# 23XXAdapter.net
KiCad netlist of a schematic drawn in EAGLE
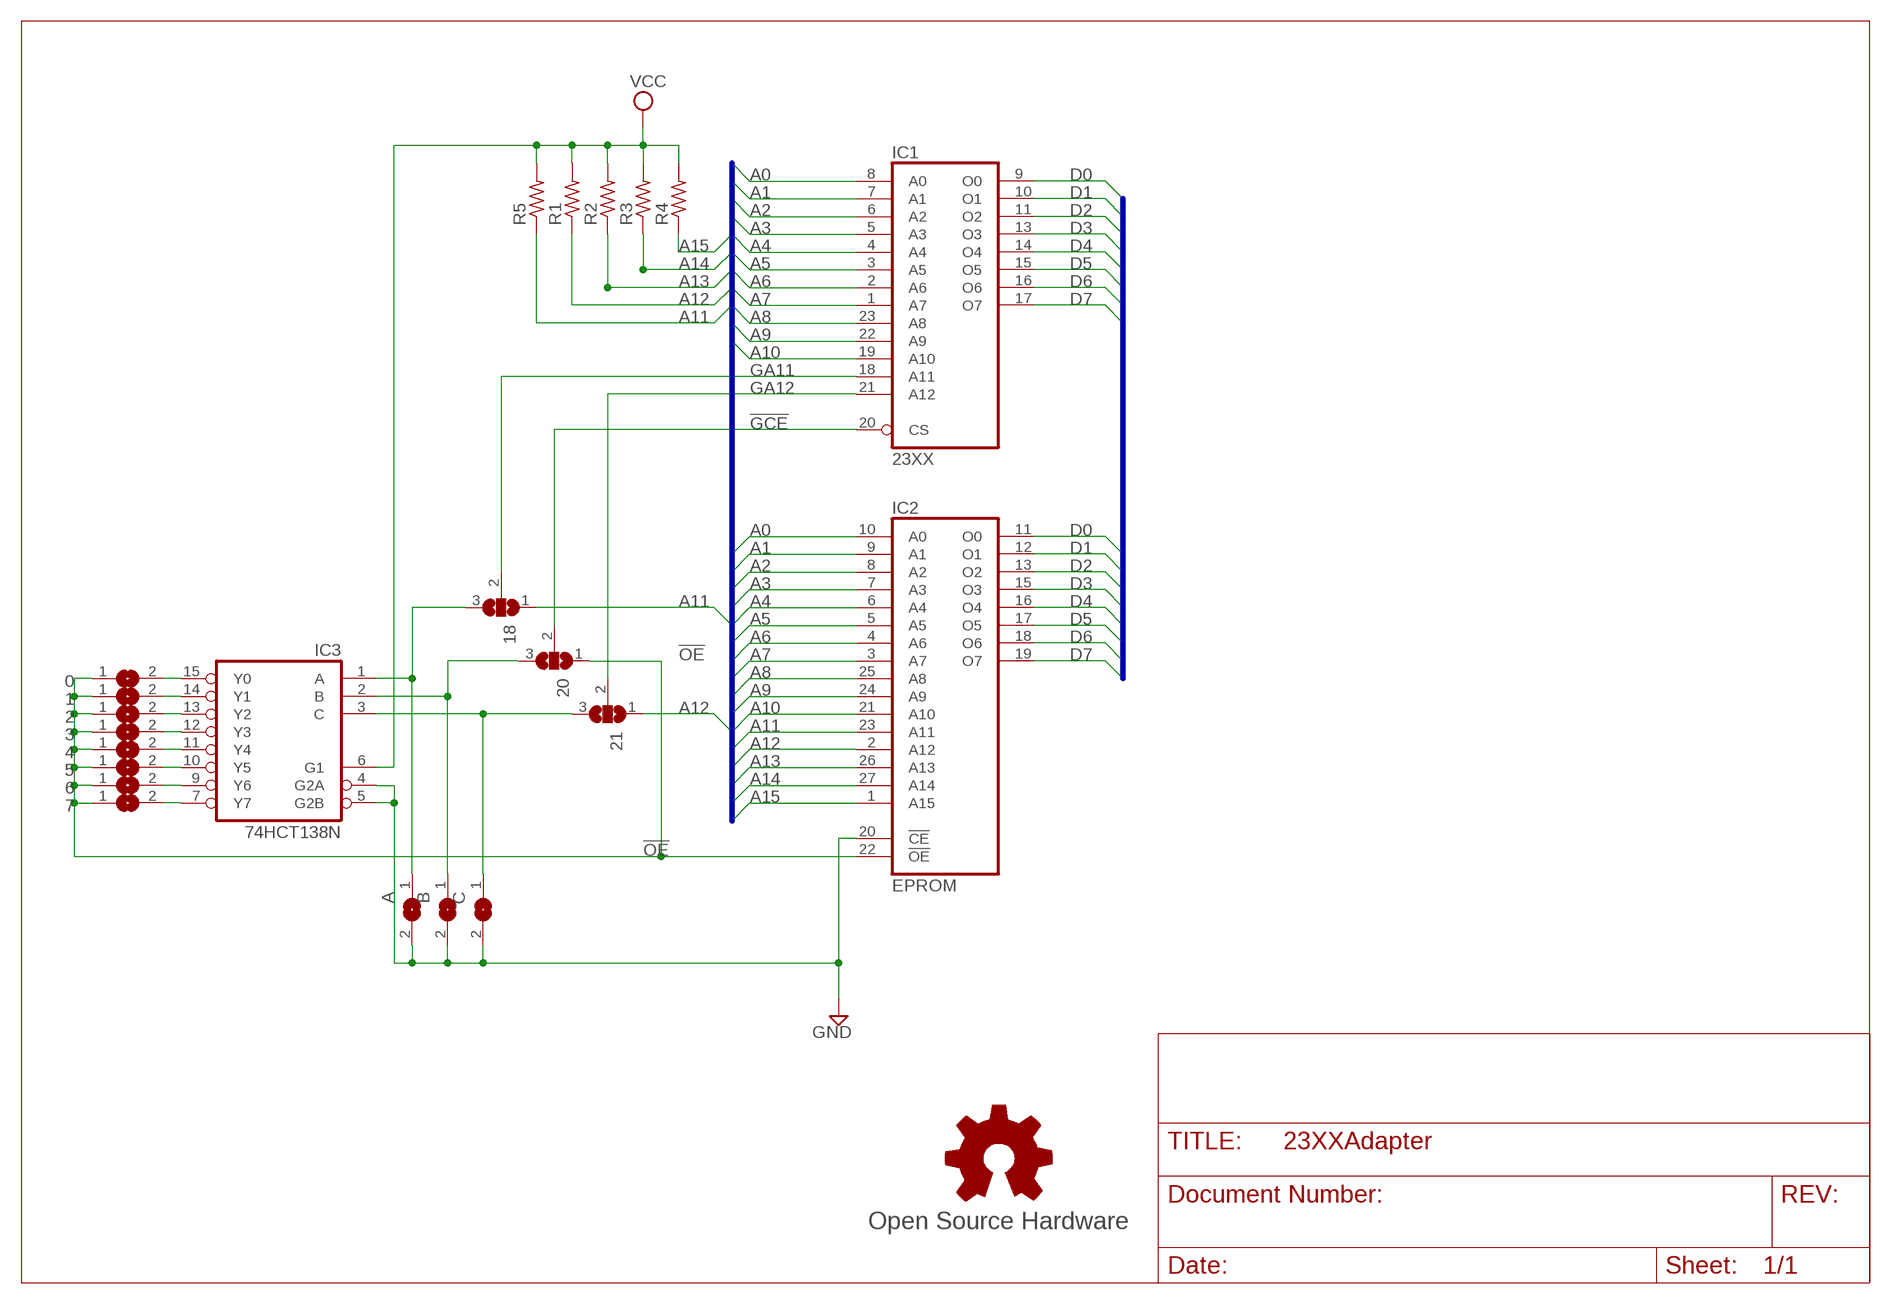
[diagram p0: schematic, sheet 1]

(export (version "E")
  (design (tool "Eeschema 10.0.6"))
  (components
    (comp (ref "0") (value "SJ") (footprint "eagle-import:SJ") (libsource (lib "eagle-import") (part "SJ")))
    (comp (ref "1") (value "SJ") (footprint "eagle-import:SJ") (libsource (lib "eagle-import") (part "SJ")))
    (comp (ref "2") (value "SJ") (footprint "eagle-import:SJ") (libsource (lib "eagle-import") (part "SJ")))
    (comp (ref "3") (value "SJ") (footprint "eagle-import:SJ") (libsource (lib "eagle-import") (part "SJ")))
    (comp (ref "4") (value "SJ") (footprint "eagle-import:SJ") (libsource (lib "eagle-import") (part "SJ")))
    (comp (ref "5") (value "SJ") (footprint "eagle-import:SJ") (libsource (lib "eagle-import") (part "SJ")))
    (comp (ref "6") (value "SJ") (footprint "eagle-import:SJ") (libsource (lib "eagle-import") (part "SJ")))
    (comp (ref "7") (value "SJ") (footprint "eagle-import:SJ") (libsource (lib "eagle-import") (part "SJ")))
    (comp (ref "18")
      (value "SJ2W")
      (footprint "eagle-import:SJ_2")
      (libsource (lib "eagle-import") (part "SJ2W"))
    )
    (comp (ref "20")
      (value "SJ2W")
      (footprint "eagle-import:SJ_2")
      (libsource (lib "eagle-import") (part "SJ2W"))
    )
    (comp (ref "21")
      (value "SJ2W")
      (footprint "eagle-import:SJ_2")
      (libsource (lib "eagle-import") (part "SJ2W"))
    )
    (comp (ref "A") (value "SJ") (footprint "eagle-import:SJ") (libsource (lib "eagle-import") (part "SJ")))
    (comp (ref "B") (value "SJ") (footprint "eagle-import:SJ") (libsource (lib "eagle-import") (part "SJ")))
    (comp (ref "C") (value "SJ") (footprint "eagle-import:SJ") (libsource (lib "eagle-import") (part "SJ")))
    (comp (ref "GOLD_ORB_SM1")
      (value "Open Source Hardware")
      (footprint "eagle-import:OSHW_5MM")
      (libsource (lib "eagle-import") (part "OSHWLOGOLOGO5MM"))
    )
    (comp (ref "IC1")
      (value "23XX")
      (footprint "eagle-import:DIL24-ROUNDPAD")
      (libsource (lib "eagle-import") (part "2364'RD'"))
    )
    (comp (ref "IC2")
      (value "EPROM")
      (footprint "eagle-import:DIL28-ROUNDPAD")
      (libsource (lib "eagle-import") (part "27512'RD'"))
    )
    (comp (ref "IC3")
      (value "74HCT138N")
      (footprint "eagle-import:DIL16")
      (libsource (lib "eagle-import") (part "74138NLS"))
    )
    (comp (ref "R1")
      (value "R-US_0204/5")
      (footprint "eagle-import:0204_5")
      (libsource (lib "eagle-import") (part "R-US_0204/5"))
    )
    (comp (ref "R2")
      (value "R-US_0204/5")
      (footprint "eagle-import:0204_5")
      (libsource (lib "eagle-import") (part "R-US_0204/5"))
    )
    (comp (ref "R3")
      (value "R-US_0204/5")
      (footprint "eagle-import:0204_5")
      (libsource (lib "eagle-import") (part "R-US_0204/5"))
    )
    (comp (ref "R4")
      (value "R-US_0204/5")
      (footprint "eagle-import:0204_5")
      (libsource (lib "eagle-import") (part "R-US_0204/5"))
    )
    (comp (ref "R5")
      (value "R-US_0204/5")
      (footprint "eagle-import:0204_5")
      (libsource (lib "eagle-import") (part "R-US_0204/5"))
    )
  )
  (nets
    (net (code "1") (name "/A0") (class "Default")
      (node (ref "IC1") (pin "8") (pinfunction "A0_8") (pintype "input"))
      (node (ref "IC2") (pin "10") (pinfunction "A0_10") (pintype "input"))
    )
    (net (code "2") (name "/A1") (class "Default")
      (node (ref "IC1") (pin "7") (pinfunction "A1_7") (pintype "input"))
      (node (ref "IC2") (pin "9") (pinfunction "A1_9") (pintype "input"))
    )
    (net (code "3") (name "/A2") (class "Default")
      (node (ref "IC1") (pin "6") (pinfunction "A2_6") (pintype "input"))
      (node (ref "IC2") (pin "8") (pinfunction "A2_8") (pintype "input"))
    )
    (net (code "4") (name "/A3") (class "Default")
      (node (ref "IC1") (pin "5") (pinfunction "A3_5") (pintype "input"))
      (node (ref "IC2") (pin "7") (pinfunction "A3_7") (pintype "input"))
    )
    (net (code "5") (name "/A4") (class "Default")
      (node (ref "IC1") (pin "4") (pinfunction "A4_4") (pintype "input"))
      (node (ref "IC2") (pin "6") (pinfunction "A4_6") (pintype "input"))
    )
    (net (code "6") (name "/A5") (class "Default")
      (node (ref "IC1") (pin "3") (pinfunction "A5_3") (pintype "input"))
      (node (ref "IC2") (pin "5") (pinfunction "A5_5") (pintype "input"))
    )
    (net (code "7") (name "/A6") (class "Default")
      (node (ref "IC1") (pin "2") (pinfunction "A6_2") (pintype "input"))
      (node (ref "IC2") (pin "4") (pinfunction "A6_4") (pintype "input"))
    )
    (net (code "8") (name "/A7") (class "Default")
      (node (ref "IC1") (pin "1") (pinfunction "A7_1") (pintype "input"))
      (node (ref "IC2") (pin "3") (pinfunction "A7_3") (pintype "input"))
    )
    (net (code "9") (name "/A8") (class "Default")
      (node (ref "IC1") (pin "23") (pinfunction "A8_23") (pintype "input"))
      (node (ref "IC2") (pin "25") (pinfunction "A8_25") (pintype "input"))
    )
    (net (code "10") (name "/A9") (class "Default")
      (node (ref "IC1") (pin "22") (pinfunction "A9_22") (pintype "input"))
      (node (ref "IC2") (pin "24") (pinfunction "A9_24") (pintype "input"))
    )
    (net (code "11") (name "/A10") (class "Default")
      (node (ref "IC1") (pin "19") (pinfunction "A10_19") (pintype "input"))
      (node (ref "IC2") (pin "21") (pinfunction "A10_21") (pintype "input"))
    )
    (net (code "12") (name "/A11") (class "Default")
      (node (ref "18") (pin "1") (pinfunction "1_1") (pintype "passive"))
      (node (ref "IC2") (pin "23") (pinfunction "A11_23") (pintype "input"))
      (node (ref "R5") (pin "1") (pinfunction "1_1") (pintype "passive"))
    )
    (net (code "13") (name "/A12") (class "Default")
      (node (ref "21") (pin "1") (pinfunction "1_1") (pintype "passive"))
      (node (ref "IC2") (pin "2") (pinfunction "A12_2") (pintype "input"))
      (node (ref "R1") (pin "1") (pinfunction "1_1") (pintype "passive"))
    )
    (net (code "14") (name "/A13") (class "Default")
      (node (ref "IC2") (pin "26") (pinfunction "A13_26") (pintype "input"))
      (node (ref "R2") (pin "1") (pinfunction "1_1") (pintype "passive"))
    )
    (net (code "15") (name "/A14") (class "Default")
      (node (ref "IC2") (pin "27") (pinfunction "A14_27") (pintype "input"))
      (node (ref "R3") (pin "1") (pinfunction "1_1") (pintype "passive"))
    )
    (net (code "16") (name "/A15") (class "Default")
      (node (ref "IC2") (pin "1") (pinfunction "A15_1") (pintype "input"))
      (node (ref "R4") (pin "1") (pinfunction "1_1") (pintype "passive"))
    )
    (net (code "17") (name "/D0") (class "Default")
      (node (ref "IC1") (pin "9") (pinfunction "O0_9") (pintype "tri_state"))
      (node (ref "IC2") (pin "11") (pinfunction "O0_11") (pintype "tri_state"))
    )
    (net (code "18") (name "/D1") (class "Default")
      (node (ref "IC1") (pin "10") (pinfunction "O1_10") (pintype "tri_state"))
      (node (ref "IC2") (pin "12") (pinfunction "O1_12") (pintype "tri_state"))
    )
    (net (code "19") (name "/D2") (class "Default")
      (node (ref "IC1") (pin "11") (pinfunction "O2_11") (pintype "tri_state"))
      (node (ref "IC2") (pin "13") (pinfunction "O2_13") (pintype "tri_state"))
    )
    (net (code "20") (name "/D3") (class "Default")
      (node (ref "IC1") (pin "13") (pinfunction "O3_13") (pintype "tri_state"))
      (node (ref "IC2") (pin "15") (pinfunction "O3_15") (pintype "tri_state"))
    )
    (net (code "21") (name "/D4") (class "Default")
      (node (ref "IC1") (pin "14") (pinfunction "O4_14") (pintype "tri_state"))
      (node (ref "IC2") (pin "16") (pinfunction "O4_16") (pintype "tri_state"))
    )
    (net (code "22") (name "/D5") (class "Default")
      (node (ref "IC1") (pin "15") (pinfunction "O5_15") (pintype "tri_state"))
      (node (ref "IC2") (pin "17") (pinfunction "O5_17") (pintype "tri_state"))
    )
    (net (code "23") (name "/D6") (class "Default")
      (node (ref "IC1") (pin "16") (pinfunction "O6_16") (pintype "tri_state"))
      (node (ref "IC2") (pin "18") (pinfunction "O6_18") (pintype "tri_state"))
    )
    (net (code "24") (name "/D7") (class "Default")
      (node (ref "IC1") (pin "17") (pinfunction "O7_17") (pintype "tri_state"))
      (node (ref "IC2") (pin "19") (pinfunction "O7_19") (pintype "tri_state"))
    )
    (net (code "25") (name "/GA11") (class "Default")
      (node (ref "18") (pin "2") (pinfunction "2_2") (pintype "passive"))
      (node (ref "IC1") (pin "18") (pinfunction "A11_18") (pintype "input"))
    )
    (net (code "26") (name "/GA12") (class "Default")
      (node (ref "21") (pin "2") (pinfunction "2_2") (pintype "passive"))
      (node (ref "IC1") (pin "21") (pinfunction "A12_21") (pintype "input"))
    )
    (net (code "27") (name "/~{GCE}") (class "Default")
      (node (ref "20") (pin "2") (pinfunction "2_2") (pintype "passive"))
      (node (ref "IC1") (pin "20") (pinfunction "CS_20") (pintype "input"))
    )
    (net (code "28") (name "/~{OE}") (class "Default")
      (node (ref "0") (pin "1") (pinfunction "1_1") (pintype "passive"))
      (node (ref "1") (pin "1") (pinfunction "1_1") (pintype "passive"))
      (node (ref "2") (pin "1") (pinfunction "1_1") (pintype "passive"))
      (node (ref "20") (pin "1") (pinfunction "1_1") (pintype "passive"))
      (node (ref "3") (pin "1") (pinfunction "1_1") (pintype "passive"))
      (node (ref "4") (pin "1") (pinfunction "1_1") (pintype "passive"))
      (node (ref "5") (pin "1") (pinfunction "1_1") (pintype "passive"))
      (node (ref "6") (pin "1") (pinfunction "1_1") (pintype "passive"))
      (node (ref "7") (pin "1") (pinfunction "1_1") (pintype "passive"))
      (node (ref "IC2") (pin "22") (pinfunction "~{OE}_22") (pintype "input"))
    )
    (net (code "29") (name "GND") (class "Default")
      (node (ref "A") (pin "2") (pinfunction "2_2") (pintype "passive"))
      (node (ref "B") (pin "2") (pinfunction "2_2") (pintype "passive"))
      (node (ref "C") (pin "2") (pinfunction "2_2") (pintype "passive"))
      (node (ref "IC2") (pin "20") (pinfunction "~{CE}_20") (pintype "input"))
      (node (ref "IC3") (pin "4") (pinfunction "G2A_4") (pintype "input"))
      (node (ref "IC3") (pin "5") (pinfunction "G2B_5") (pintype "input"))
    )
    (net (code "30") (name "Net-(IC3A-A)") (class "Default")
      (node (ref "18") (pin "3") (pinfunction "3_3") (pintype "passive"))
      (node (ref "A") (pin "1") (pinfunction "1_1") (pintype "passive"))
      (node (ref "IC3") (pin "1") (pinfunction "A_1") (pintype "input"))
    )
    (net (code "31") (name "Net-(IC3A-B)") (class "Default")
      (node (ref "20") (pin "3") (pinfunction "3_3") (pintype "passive"))
      (node (ref "B") (pin "1") (pinfunction "1_1") (pintype "passive"))
      (node (ref "IC3") (pin "2") (pinfunction "B_2") (pintype "input"))
    )
    (net (code "32") (name "Net-(IC3A-C)") (class "Default")
      (node (ref "21") (pin "3") (pinfunction "3_3") (pintype "passive"))
      (node (ref "C") (pin "1") (pinfunction "1_1") (pintype "passive"))
      (node (ref "IC3") (pin "3") (pinfunction "C_3") (pintype "input"))
    )
    (net (code "33") (name "Net-(IC3A-Y0)") (class "Default")
      (node (ref "0") (pin "2") (pinfunction "2_2") (pintype "passive"))
      (node (ref "IC3") (pin "15") (pinfunction "Y0_15") (pintype "output"))
    )
    (net (code "34") (name "Net-(IC3A-Y1)") (class "Default")
      (node (ref "1") (pin "2") (pinfunction "2_2") (pintype "passive"))
      (node (ref "IC3") (pin "14") (pinfunction "Y1_14") (pintype "output"))
    )
    (net (code "35") (name "Net-(IC3A-Y2)") (class "Default")
      (node (ref "2") (pin "2") (pinfunction "2_2") (pintype "passive"))
      (node (ref "IC3") (pin "13") (pinfunction "Y2_13") (pintype "output"))
    )
    (net (code "36") (name "Net-(IC3A-Y3)") (class "Default")
      (node (ref "3") (pin "2") (pinfunction "2_2") (pintype "passive"))
      (node (ref "IC3") (pin "12") (pinfunction "Y3_12") (pintype "output"))
    )
    (net (code "37") (name "Net-(IC3A-Y4)") (class "Default")
      (node (ref "4") (pin "2") (pinfunction "2_2") (pintype "passive"))
      (node (ref "IC3") (pin "11") (pinfunction "Y4_11") (pintype "output"))
    )
    (net (code "38") (name "Net-(IC3A-Y5)") (class "Default")
      (node (ref "5") (pin "2") (pinfunction "2_2") (pintype "passive"))
      (node (ref "IC3") (pin "10") (pinfunction "Y5_10") (pintype "output"))
    )
    (net (code "39") (name "Net-(IC3A-Y6)") (class "Default")
      (node (ref "6") (pin "2") (pinfunction "2_2") (pintype "passive"))
      (node (ref "IC3") (pin "9") (pinfunction "Y6_9") (pintype "output"))
    )
    (net (code "40") (name "Net-(IC3A-Y7)") (class "Default")
      (node (ref "7") (pin "2") (pinfunction "2_2") (pintype "passive"))
      (node (ref "IC3") (pin "7") (pinfunction "Y7_7") (pintype "output"))
    )
    (net (code "41") (name "VCC") (class "Default")
      (node (ref "IC3") (pin "6") (pinfunction "G1_6") (pintype "input"))
      (node (ref "R1") (pin "2") (pinfunction "2_2") (pintype "passive"))
      (node (ref "R2") (pin "2") (pinfunction "2_2") (pintype "passive"))
      (node (ref "R3") (pin "2") (pinfunction "2_2") (pintype "passive"))
      (node (ref "R4") (pin "2") (pinfunction "2_2") (pintype "passive"))
      (node (ref "R5") (pin "2") (pinfunction "2_2") (pintype "passive"))
    )
  )
)
